# Motor_Driver_1.net
KiCad netlist of a schematic drawn in Altium Designer
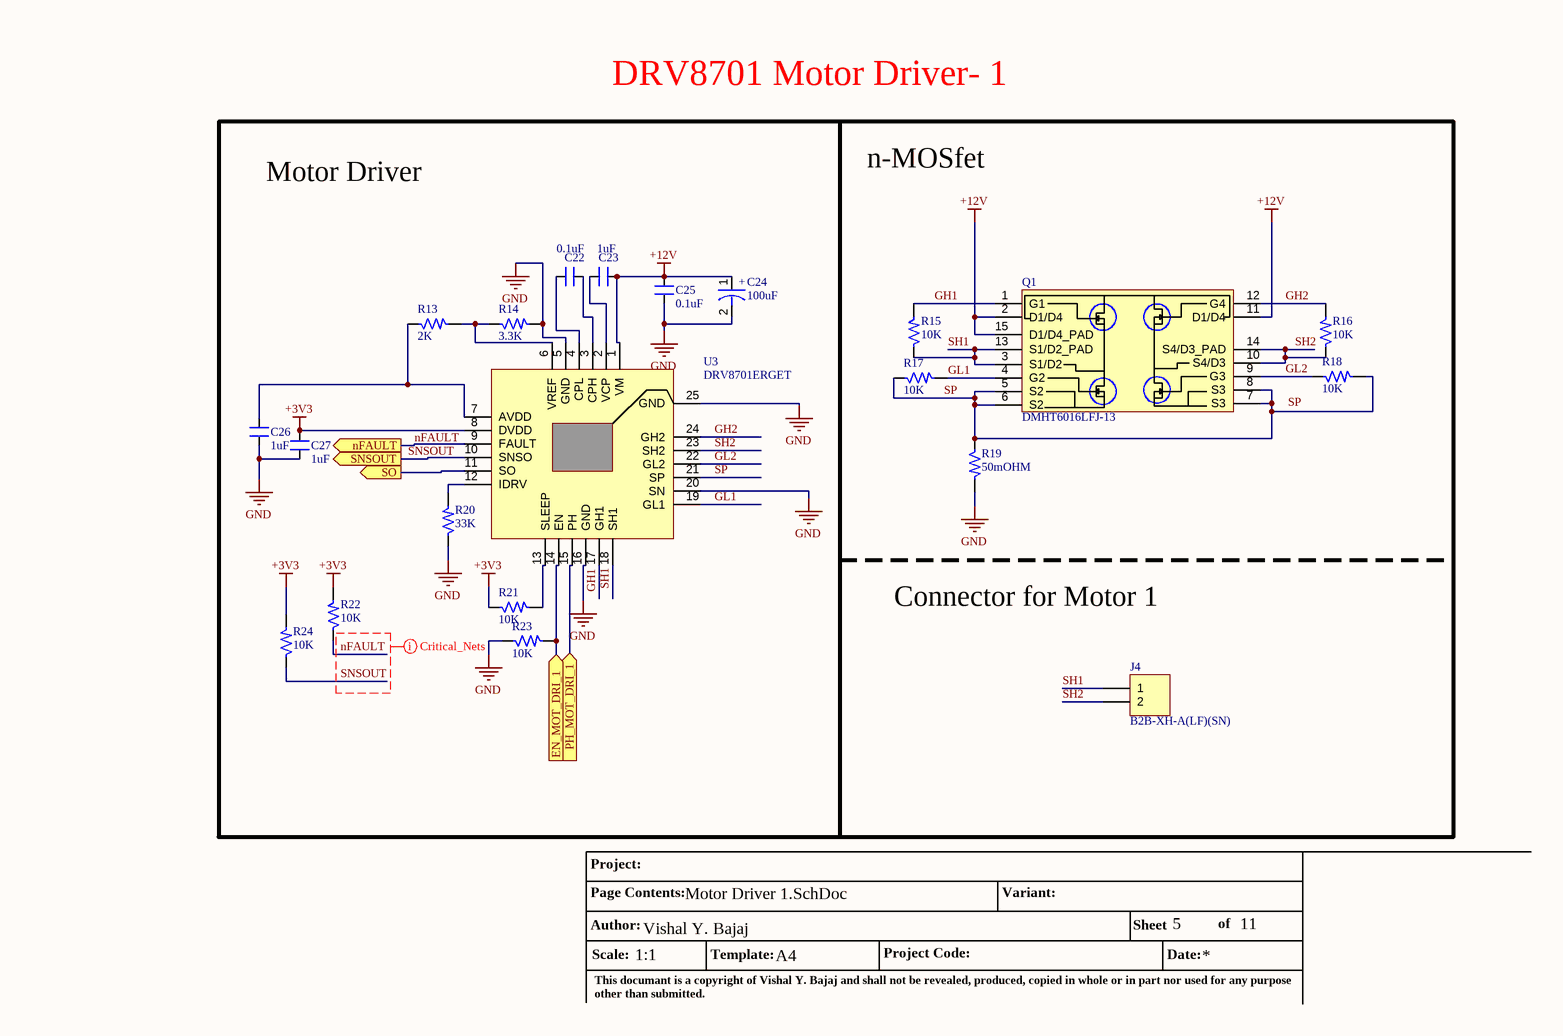
[diagram p0: Motor Driver 1.SchDoc]

(export (version "E")
  (design (tool "Eeschema 10.0.6"))
  (components
    (comp (ref "C22")
      (value "0.1uF")
      (footprint "CAP_0805")
      (description "0.1µF ±10% 50V Ceramic Capacitor X7R 0805 (2012 Metric)")
      (fields
        (field (name "MANUFACTURER") "Samsung")
        (field (name "MANUFACTURER PART NUMBER") "CL21B104KBCNNNC")
      )
      (libsource (lib "ESTEEMPCBLIB") (part "CAP_0.1uF-50V-10%-0805"))
    )
    (comp (ref "C23")
      (value "1uF")
      (footprint "CAP_0805")
      (description "1µF ±5% 50V Ceramic Capacitor X7R 0805 (2012 Metric)")
      (fields
        (field (name "MANUFACTURER") "Samsung")
        (field (name "MANUFACTURER PART NUMBER") "CC0805JKX7R9BB105")
      )
      (libsource (lib "ESTEEMPCBLIB") (part "CAP_1uF-50V-5%-0805"))
    )
    (comp (ref "C24")
      (value "100uF")
      (footprint "ACAP_P236_D305_H303_RAD")
      (description "100µF 25V Aluminum Electrolytic Capacitors Radial, Can - SMD 1000 Hrs @ 105°C")
      (fields
        (field (name "MANUFACTURER") "Nichicon")
        (field (name "MANUFACTURER PART NUMBER") "UWT1E101MCL1GS")
      )
      (libsource (lib "ESTEEMPCBLIB") (part "CAP-P_100uF-25V-20%-RAD"))
    )
    (comp (ref "C25")
      (value "0.1uF")
      (footprint "CAP_0805")
      (description "0.1µF ±10% 50V Ceramic Capacitor X7R 0805 (2012 Metric)")
      (fields
        (field (name "MANUFACTURER") "Samsung")
        (field (name "MANUFACTURER PART NUMBER") "CL21B104KBCNNNC")
      )
      (libsource (lib "ESTEEMPCBLIB") (part "CAP_0.1uF-50V-10%-0805"))
    )
    (comp (ref "C26")
      (value "1uF")
      (footprint "CAP_0805")
      (description "1µF ±5% 50V Ceramic Capacitor X7R 0805 (2012 Metric)")
      (fields
        (field (name "MANUFACTURER") "Samsung")
        (field (name "MANUFACTURER PART NUMBER") "CC0805JKX7R9BB105")
      )
      (libsource (lib "ESTEEMPCBLIB") (part "CAP_1uF-50V-5%-0805"))
    )
    (comp (ref "C27")
      (value "1uF")
      (footprint "CAP_0805")
      (description "1µF ±5% 50V Ceramic Capacitor X7R 0805 (2012 Metric)")
      (fields
        (field (name "MANUFACTURER") "Samsung")
        (field (name "MANUFACTURER PART NUMBER") "CC0805JKX7R9BB105")
      )
      (libsource (lib "ESTEEMPCBLIB") (part "CAP_1uF-50V-5%-0805"))
    )
    (comp (ref "J4")
      (value "B2B-XH-A(LF)(SN)")
      (footprint "CON2_100_B2B-XH-A_TH_ST")
      (description "2 Pins, 1 Row 2.54mm Pitch, Straight Connector, male")
      (fields (field (name "MANUFACTURER") "JST") (field (name "MATING PART NUMBER") "XHP-2"))
      (libsource (lib "ESTEEMPCBLIB") (part "CON-PLG_2X1-100-ST-TH"))
    )
    (comp (ref "Q1")
      (value "DMHT6016LFJ-13")
      (footprint "DFN5045-12_33_212_27X15_SMD_1")
      (description "Mosfet Array 4 N-Channel 14.8A (Ta) Surface Mount V-DFN5045-12")
      (fields (field (name "MANUFACTURER") "ON Semiconductor"))
      (libsource (lib "ESTEEMPCBLIB") (part "MOSFET-N_60V-14.8A-V-DFN5045-12"))
    )
    (comp (ref "R13")
      (value "2K")
      (footprint "RES_0805")
      (description "2 kOhms ±1% 0.125W, 1/8W Chip Resistor 0805 (2012 Metric) Moisture Resistant Thick Film")
      (fields
        (field (name "MANUFACTURER") "TE Connectivity")
        (field (name "MANUFACTURER PART NUMBER") "RC0805FR-072KL")
      )
      (libsource (lib "ESTEEMPCBLIB") (part "RES_2K-0.125W-1%-0805"))
    )
    (comp (ref "R14")
      (value "3.3K")
      (footprint "RES_0805")
      (description "3.3 kOhms ±1% 0.125W, 1/8W Chip Resistor 0805 (2012 Metric) Thick Film")
      (fields (field (name "MANUFACTURER") "Panasonic") (field (name "MANUFACTURER PART NUMBER") "1623214-1"))
      (libsource (lib "ESTEEMPCBLIB") (part "RES_3.3K-0.125W-1%-0805"))
    )
    (comp (ref "R15")
      (value "10K")
      (footprint "RES_0603")
      (description "10 kOhms ±1% 0.1W, 1/10W Chip Resistor 0603 (1608 Metric) Automotive AEC-Q200 Thick Film")
      (fields (field (name "MANUFACTURER") "Walsin") (field (name "MANUFACTURER PART NUMBER") "WR06X1002FTL"))
      (libsource (lib "ESTEEMPCBLIB") (part "RES_10K-0.1W-1%-0603"))
    )
    (comp (ref "R16")
      (value "10K")
      (footprint "RES_0603")
      (description "10 kOhms ±1% 0.1W, 1/10W Chip Resistor 0603 (1608 Metric) Automotive AEC-Q200 Thick Film")
      (fields (field (name "MANUFACTURER") "Walsin") (field (name "MANUFACTURER PART NUMBER") "WR06X1002FTL"))
      (libsource (lib "ESTEEMPCBLIB") (part "RES_10K-0.1W-1%-0603"))
    )
    (comp (ref "R17")
      (value "10K")
      (footprint "RES_0603")
      (description "10 kOhms ±1% 0.1W, 1/10W Chip Resistor 0603 (1608 Metric) Automotive AEC-Q200 Thick Film")
      (fields (field (name "MANUFACTURER") "Walsin") (field (name "MANUFACTURER PART NUMBER") "WR06X1002FTL"))
      (libsource (lib "ESTEEMPCBLIB") (part "RES_10K-0.1W-1%-0603"))
    )
    (comp (ref "R18")
      (value "10K")
      (footprint "RES_0603")
      (description "10 kOhms ±1% 0.1W, 1/10W Chip Resistor 0603 (1608 Metric) Automotive AEC-Q200 Thick Film")
      (fields (field (name "MANUFACTURER") "Walsin") (field (name "MANUFACTURER PART NUMBER") "WR06X1002FTL"))
      (libsource (lib "ESTEEMPCBLIB") (part "RES_10K-0.1W-1%-0603"))
    )
    (comp (ref "R19")
      (value "50mOHM")
      (footprint "RES_2512")
      (fields
        (field (name "MANUFACTURER") "Yageo")
        (field (name "MANUFACTURER PART NUMBER") "PA2512FKF7W0R05E")
      )
      (libsource (lib "ESTEEMPCBLIB") (part "RES_50mOhm-2W-1%-2512"))
    )
    (comp (ref "R20")
      (value "33K")
      (footprint "RES_0805")
      (fields
        (field (name "MANUFACTURER") "Vishay BCcomponents")
        (field (name "MANUFACTURER PART NUMBER") "CRG0805F33K")
      )
      (libsource (lib "ESTEEMPCBLIB") (part "RES_33K-0.125W-1%-0805"))
    )
    (comp (ref "R21")
      (value "10K")
      (footprint "RES_0603")
      (description "10 kOhms ±1% 0.1W, 1/10W Chip Resistor 0603 (1608 Metric) Automotive AEC-Q200 Thick Film")
      (fields (field (name "MANUFACTURER") "Walsin") (field (name "MANUFACTURER PART NUMBER") "WR06X1002FTL"))
      (libsource (lib "ESTEEMPCBLIB") (part "RES_10K-0.1W-1%-0603"))
    )
    (comp (ref "R22")
      (value "10K")
      (footprint "RES_0805")
      (description "10 kOhms ±1% 0.125W, 1/8W Chip Resistor 0805 (2012 Metric) Automotive AEC-Q200 Thick Film")
      (fields (field (name "MANUFACTURER") "CTS") (field (name "MANUFACTURER PART NUMBER") "WR08X1002FTL"))
      (libsource (lib "ESTEEMPCBLIB") (part "RES_10K-0.125W-1%-0805"))
    )
    (comp (ref "R23")
      (value "10K")
      (footprint "RES_0603")
      (description "10 kOhms ±1% 0.1W, 1/10W Chip Resistor 0603 (1608 Metric) Automotive AEC-Q200 Thick Film")
      (fields (field (name "MANUFACTURER") "Walsin") (field (name "MANUFACTURER PART NUMBER") "WR06X1002FTL"))
      (libsource (lib "ESTEEMPCBLIB") (part "RES_10K-0.1W-1%-0603"))
    )
    (comp (ref "R24")
      (value "10K")
      (footprint "RES_0805")
      (description "10 kOhms ±1% 0.125W, 1/8W Chip Resistor 0805 (2012 Metric) Automotive AEC-Q200 Thick Film")
      (fields (field (name "MANUFACTURER") "CTS") (field (name "MANUFACTURER PART NUMBER") "WR08X1002FTL"))
      (libsource (lib "ESTEEMPCBLIB") (part "RES_10K-0.125W-1%-0805"))
    )
    (comp (ref "U3")
      (value "DRV8701ERGET")
      (footprint "VFQFN24_19.6_196_12X32_SMD_1")
      (description "Motor Driver Power MOSFET Parallel 24-VQFN (4x4)")
      (fields (field (name "MANUFACTURER") "Texas Instruments"))
      (libsource (lib "ESTEEMPCBLIB") (part "IC_DRV8701ERGET"))
    )
  )
  (nets
    (net (code "1") (name "+3V3") (class "Default")
      (node (ref "C27") (pin "2") (pinfunction "2_2") (pintype "passive"))
      (node (ref "R21") (pin "1") (pinfunction "1_1") (pintype "passive"))
      (node (ref "R22") (pin "2") (pinfunction "2_2") (pintype "passive"))
      (node (ref "R24") (pin "2") (pinfunction "2_2") (pintype "passive"))
      (node (ref "U3") (pin "8") (pinfunction "DVDD_8") (pintype "passive"))
    )
    (net (code "2") (name "+12V") (class "Default")
      (node (ref "C23") (pin "2") (pinfunction "2_2") (pintype "passive"))
      (node (ref "C24") (pin "1") (pinfunction "1_1") (pintype "passive"))
      (node (ref "C25") (pin "2") (pinfunction "2_2") (pintype "passive"))
      (node (ref "Q1") (pin "11") (pinfunction "D1/D4_11") (pintype "passive"))
      (node (ref "Q1") (pin "15") (pinfunction "D1/D4_PAD_15") (pintype "passive"))
      (node (ref "Q1") (pin "2") (pinfunction "D1/D4_2") (pintype "passive"))
      (node (ref "U3") (pin "1") (pinfunction "VM_1") (pintype "passive"))
    )
    (net (code "3") (name "/EN_MOT_DRI_1") (class "Default")
      (node (ref "R23") (pin "2") (pinfunction "2_2") (pintype "passive"))
      (node (ref "U3") (pin "14") (pinfunction "EN_14") (pintype "passive"))
    )
    (net (code "4") (name "/GH1") (class "Default")
      (node (ref "Q1") (pin "1") (pinfunction "G1_1") (pintype "passive"))
      (node (ref "R15") (pin "2") (pinfunction "2_2") (pintype "passive"))
      (node (ref "U3") (pin "17") (pinfunction "GH1_17") (pintype "passive"))
    )
    (net (code "5") (name "/GH2") (class "Default")
      (node (ref "Q1") (pin "12") (pinfunction "G4_12") (pintype "passive"))
      (node (ref "R16") (pin "2") (pinfunction "2_2") (pintype "passive"))
      (node (ref "U3") (pin "24") (pinfunction "GH2_24") (pintype "passive"))
    )
    (net (code "6") (name "/GL1") (class "Default")
      (node (ref "Q1") (pin "4") (pinfunction "G2_4") (pintype "passive"))
      (node (ref "R17") (pin "2") (pinfunction "2_2") (pintype "passive"))
      (node (ref "U3") (pin "19") (pinfunction "GL1_19") (pintype "passive"))
    )
    (net (code "7") (name "/GL2") (class "Default")
      (node (ref "Q1") (pin "9") (pinfunction "G3_9") (pintype "passive"))
      (node (ref "R18") (pin "1") (pinfunction "1_1") (pintype "passive"))
      (node (ref "U3") (pin "22") (pinfunction "GL2_22") (pintype "passive"))
    )
    (net (code "8") (name "/PH_MOT_DRI_1") (class "Default")
      (node (ref "U3") (pin "15") (pinfunction "PH_15") (pintype "passive"))
    )
    (net (code "9") (name "/SH1") (class "Default")
      (node (ref "J4") (pin "1") (pinfunction "1_1") (pintype "passive"))
      (node (ref "Q1") (pin "13") (pinfunction "S1/D2_PAD_13") (pintype "passive"))
      (node (ref "Q1") (pin "3") (pinfunction "S1/D2_3") (pintype "passive"))
      (node (ref "R15") (pin "1") (pinfunction "1_1") (pintype "passive"))
      (node (ref "U3") (pin "18") (pinfunction "SH1_18") (pintype "passive"))
    )
    (net (code "10") (name "/SH2") (class "Default")
      (node (ref "J4") (pin "2") (pinfunction "2_2") (pintype "passive"))
      (node (ref "Q1") (pin "10") (pinfunction "S4/D3_10") (pintype "passive"))
      (node (ref "Q1") (pin "14") (pinfunction "S4/D3_PAD_14") (pintype "passive"))
      (node (ref "R16") (pin "1") (pinfunction "1_1") (pintype "passive"))
      (node (ref "U3") (pin "23") (pinfunction "SH2_23") (pintype "passive"))
    )
    (net (code "11") (name "/SNSOUT") (class "Default")
      (node (ref "R24") (pin "1") (pinfunction "1_1") (pintype "passive"))
      (node (ref "U3") (pin "10") (pinfunction "SNSO_10") (pintype "passive"))
    )
    (net (code "12") (name "/SO") (class "Default")
      (node (ref "U3") (pin "11") (pinfunction "SO_11") (pintype "passive"))
    )
    (net (code "13") (name "/SP") (class "Default")
      (node (ref "Q1") (pin "5") (pinfunction "S2_5") (pintype "passive"))
      (node (ref "Q1") (pin "6") (pinfunction "S2_6") (pintype "passive"))
      (node (ref "Q1") (pin "7") (pinfunction "S3_7") (pintype "passive"))
      (node (ref "Q1") (pin "8") (pinfunction "S3_8") (pintype "passive"))
      (node (ref "R17") (pin "1") (pinfunction "1_1") (pintype "passive"))
      (node (ref "R18") (pin "2") (pinfunction "2_2") (pintype "passive"))
      (node (ref "R19") (pin "1") (pinfunction "1_1") (pintype "passive"))
      (node (ref "U3") (pin "21") (pinfunction "SP_21") (pintype "passive"))
    )
    (net (code "14") (name "/nFAULT") (class "Default")
      (node (ref "R22") (pin "1") (pinfunction "1_1") (pintype "passive"))
      (node (ref "U3") (pin "9") (pinfunction "FAULT_9") (pintype "passive"))
    )
    (net (code "15") (name "GND") (class "Default")
      (node (ref "C24") (pin "2") (pinfunction "2_2") (pintype "passive"))
      (node (ref "C25") (pin "1") (pinfunction "1_1") (pintype "passive"))
      (node (ref "C26") (pin "1") (pinfunction "1_1") (pintype "passive"))
      (node (ref "C27") (pin "1") (pinfunction "1_1") (pintype "passive"))
      (node (ref "R14") (pin "2") (pinfunction "2_2") (pintype "passive"))
      (node (ref "R19") (pin "2") (pinfunction "2_2") (pintype "passive"))
      (node (ref "R20") (pin "1") (pinfunction "1_1") (pintype "passive"))
      (node (ref "R23") (pin "1") (pinfunction "1_1") (pintype "passive"))
      (node (ref "U3") (pin "16") (pinfunction "GND_16") (pintype "passive"))
      (node (ref "U3") (pin "20") (pinfunction "SN_20") (pintype "passive"))
      (node (ref "U3") (pin "25") (pinfunction "GND_25") (pintype "passive"))
      (node (ref "U3") (pin "5") (pinfunction "GND_5") (pintype "passive"))
    )
    (net (code "16") (name "Net-(U3-AVDD)") (class "Default")
      (node (ref "C26") (pin "2") (pinfunction "2_2") (pintype "passive"))
      (node (ref "R13") (pin "1") (pinfunction "1_1") (pintype "passive"))
      (node (ref "U3") (pin "7") (pinfunction "AVDD_7") (pintype "passive"))
    )
    (net (code "17") (name "Net-(U3-CPH)") (class "Default")
      (node (ref "C22") (pin "1") (pinfunction "1_1") (pintype "passive"))
      (node (ref "U3") (pin "3") (pinfunction "CPH_3") (pintype "passive"))
    )
    (net (code "18") (name "Net-(U3-CPL)") (class "Default")
      (node (ref "C22") (pin "2") (pinfunction "2_2") (pintype "passive"))
      (node (ref "U3") (pin "4") (pinfunction "CPL_4") (pintype "passive"))
    )
    (net (code "19") (name "Net-(U3-IDRV)") (class "Default")
      (node (ref "R20") (pin "2") (pinfunction "2_2") (pintype "passive"))
      (node (ref "U3") (pin "12") (pinfunction "IDRV_12") (pintype "passive"))
    )
    (net (code "20") (name "Net-(U3-SLEEP)") (class "Default")
      (node (ref "R21") (pin "2") (pinfunction "2_2") (pintype "passive"))
      (node (ref "U3") (pin "13") (pinfunction "SLEEP_13") (pintype "passive"))
    )
    (net (code "21") (name "Net-(U3-VCP)") (class "Default")
      (node (ref "C23") (pin "1") (pinfunction "1_1") (pintype "passive"))
      (node (ref "U3") (pin "2") (pinfunction "VCP_2") (pintype "passive"))
    )
    (net (code "22") (name "Net-(U3-VREF)") (class "Default")
      (node (ref "R13") (pin "2") (pinfunction "2_2") (pintype "passive"))
      (node (ref "R14") (pin "1") (pinfunction "1_1") (pintype "passive"))
      (node (ref "U3") (pin "6") (pinfunction "VREF_6") (pintype "passive"))
    )
  )
)
